# M207.net
KiCad netlist of a schematic drawn in EAGLE
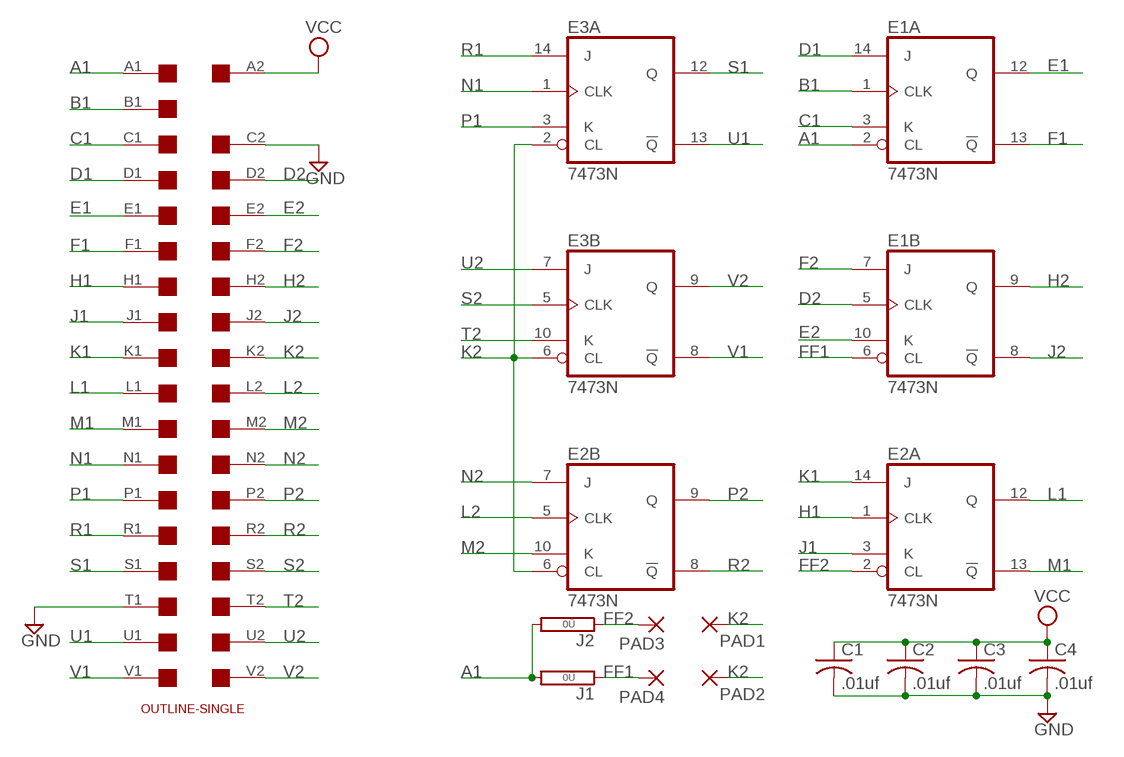
[diagram p0: schematic, sheet 1]

(export (version "E")
  (design (tool "Eeschema 10.0.6"))
  (components
    (comp (ref "C1")
      (value ".01uf")
      (footprint "eagle-import:C050-025X075")
      (libsource (lib "eagle-import") (part "C-US050-025X075"))
    )
    (comp (ref "C2")
      (value ".01uf")
      (footprint "eagle-import:C050-025X075")
      (libsource (lib "eagle-import") (part "C-US050-025X075"))
    )
    (comp (ref "C3")
      (value ".01uf")
      (footprint "eagle-import:C050-025X075")
      (libsource (lib "eagle-import") (part "C-US050-025X075"))
    )
    (comp (ref "C4")
      (value ".01uf")
      (footprint "eagle-import:C050-025X075")
      (libsource (lib "eagle-import") (part "C-US050-025X075"))
    )
    (comp (ref "E1")
      (value "7473N")
      (footprint "eagle-import:DIL14")
      (libsource (lib "eagle-import") (part "7473NLS"))
    )
    (comp (ref "E2")
      (value "7473N")
      (footprint "eagle-import:DIL14")
      (libsource (lib "eagle-import") (part "7473NLS"))
    )
    (comp (ref "E3")
      (value "7473N")
      (footprint "eagle-import:DIL14")
      (libsource (lib "eagle-import") (part "7473NLS"))
    )
    (comp (ref "J1")
      (value "0R")
      (footprint "eagle-import:0R_10")
      (libsource (lib "eagle-import") (part "0R"))
    )
    (comp (ref "J2")
      (value "0R")
      (footprint "eagle-import:0R_10")
      (libsource (lib "eagle-import") (part "0R"))
    )
    (comp (ref "PAD1")
      (value "1,6/0,8")
      (footprint "eagle-import:1,6_0,8")
      (libsource (lib "eagle-import") (part "1,6/0,8"))
    )
    (comp (ref "PAD2")
      (value "1,6/0,8")
      (footprint "eagle-import:1,6_0,8")
      (libsource (lib "eagle-import") (part "1,6/0,8"))
    )
    (comp (ref "PAD3")
      (value "1,6/0,8")
      (footprint "eagle-import:1,6_0,8")
      (libsource (lib "eagle-import") (part "1,6/0,8"))
    )
    (comp (ref "PAD4")
      (value "1,6/0,8")
      (footprint "eagle-import:1,6_0,8")
      (libsource (lib "eagle-import") (part "1,6/0,8"))
    )
    (comp (ref "U$1")
      (value "SINGLE")
      (footprint "eagle-import:EDGE-CON2")
      (libsource (lib "eagle-import") (part "SINGLE"))
    )
    (comp (ref "U$4")
      (value "OUTLINE-SINGLE")
      (footprint "eagle-import:SINGLE")
      (libsource (lib "eagle-import") (part "OUTLINE-SINGLE"))
    )
  )
  (nets
    (net (code "1") (name "/A1") (class "Default")
      (node (ref "E1") (pin "2") (pinfunction "CL_2") (pintype "input"))
      (node (ref "J1") (pin "2") (pinfunction "2_2") (pintype "passive"))
      (node (ref "J2") (pin "2") (pinfunction "2_2") (pintype "passive"))
      (node (ref "U$1") (pin "A1") (pinfunction "1_A1") (pintype "bidirectional"))
    )
    (net (code "2") (name "/B1") (class "Default")
      (node (ref "E1") (pin "1") (pinfunction "CLK_1") (pintype "input"))
      (node (ref "U$1") (pin "B1") (pinfunction "1_B1") (pintype "bidirectional"))
    )
    (net (code "3") (name "/C1") (class "Default")
      (node (ref "E1") (pin "3") (pinfunction "K_3") (pintype "input"))
      (node (ref "U$1") (pin "C1") (pinfunction "1_C1") (pintype "bidirectional"))
    )
    (net (code "4") (name "/D1") (class "Default")
      (node (ref "E1") (pin "14") (pinfunction "J_14") (pintype "input"))
      (node (ref "U$1") (pin "D1") (pinfunction "1_D1") (pintype "bidirectional"))
    )
    (net (code "5") (name "/D2") (class "Default")
      (node (ref "E1") (pin "5") (pinfunction "CLK_5") (pintype "input"))
      (node (ref "U$1") (pin "D2") (pinfunction "1_D2") (pintype "bidirectional"))
    )
    (net (code "6") (name "/E1") (class "Default")
      (node (ref "E1") (pin "12") (pinfunction "Q_12") (pintype "output"))
      (node (ref "U$1") (pin "E1") (pinfunction "1_E1") (pintype "bidirectional"))
    )
    (net (code "7") (name "/E2") (class "Default")
      (node (ref "E1") (pin "10") (pinfunction "K_10") (pintype "input"))
      (node (ref "U$1") (pin "E2") (pinfunction "1_E2") (pintype "bidirectional"))
    )
    (net (code "8") (name "/F1") (class "Default")
      (node (ref "E1") (pin "13") (pinfunction "~{Q}_13") (pintype "output"))
      (node (ref "U$1") (pin "F1") (pinfunction "1_F1") (pintype "bidirectional"))
    )
    (net (code "9") (name "/F2") (class "Default")
      (node (ref "E1") (pin "7") (pinfunction "J_7") (pintype "input"))
      (node (ref "U$1") (pin "F2") (pinfunction "1_F2") (pintype "bidirectional"))
    )
    (net (code "10") (name "/FF1") (class "Default")
      (node (ref "E1") (pin "6") (pinfunction "CL_6") (pintype "input"))
      (node (ref "J1") (pin "1") (pinfunction "1_1") (pintype "passive"))
      (node (ref "PAD4") (pin "1") (pinfunction "P_1") (pintype "passive"))
    )
    (net (code "11") (name "/FF2") (class "Default")
      (node (ref "E2") (pin "2") (pinfunction "CL_2") (pintype "input"))
      (node (ref "J2") (pin "1") (pinfunction "1_1") (pintype "passive"))
      (node (ref "PAD3") (pin "1") (pinfunction "P_1") (pintype "passive"))
    )
    (net (code "12") (name "/H1") (class "Default")
      (node (ref "E2") (pin "1") (pinfunction "CLK_1") (pintype "input"))
      (node (ref "U$1") (pin "H1") (pinfunction "1_H1") (pintype "bidirectional"))
    )
    (net (code "13") (name "/H2") (class "Default")
      (node (ref "E1") (pin "9") (pinfunction "Q_9") (pintype "output"))
      (node (ref "U$1") (pin "H2") (pinfunction "1_H2") (pintype "bidirectional"))
    )
    (net (code "14") (name "/J1") (class "Default")
      (node (ref "E2") (pin "3") (pinfunction "K_3") (pintype "input"))
      (node (ref "U$1") (pin "J1") (pinfunction "1_J1") (pintype "bidirectional"))
    )
    (net (code "15") (name "/J2") (class "Default")
      (node (ref "E1") (pin "8") (pinfunction "~{Q}_8") (pintype "output"))
      (node (ref "U$1") (pin "J2") (pinfunction "1_J2") (pintype "bidirectional"))
    )
    (net (code "16") (name "/K1") (class "Default")
      (node (ref "E2") (pin "14") (pinfunction "J_14") (pintype "input"))
      (node (ref "U$1") (pin "K1") (pinfunction "1_K1") (pintype "bidirectional"))
    )
    (net (code "17") (name "/K2") (class "Default")
      (node (ref "E2") (pin "6") (pinfunction "CL_6") (pintype "input"))
      (node (ref "E3") (pin "2") (pinfunction "CL_2") (pintype "input"))
      (node (ref "E3") (pin "6") (pinfunction "CL_6") (pintype "input"))
      (node (ref "PAD1") (pin "1") (pinfunction "P_1") (pintype "passive"))
      (node (ref "PAD2") (pin "1") (pinfunction "P_1") (pintype "passive"))
      (node (ref "U$1") (pin "K2") (pinfunction "1_K2") (pintype "bidirectional"))
    )
    (net (code "18") (name "/L1") (class "Default")
      (node (ref "E2") (pin "12") (pinfunction "Q_12") (pintype "output"))
      (node (ref "U$1") (pin "L1") (pinfunction "1_L1") (pintype "bidirectional"))
    )
    (net (code "19") (name "/L2") (class "Default")
      (node (ref "E2") (pin "5") (pinfunction "CLK_5") (pintype "input"))
      (node (ref "U$1") (pin "L2") (pinfunction "1_L2") (pintype "bidirectional"))
    )
    (net (code "20") (name "/M1") (class "Default")
      (node (ref "E2") (pin "13") (pinfunction "~{Q}_13") (pintype "output"))
      (node (ref "U$1") (pin "M1") (pinfunction "1_M1") (pintype "bidirectional"))
    )
    (net (code "21") (name "/M2") (class "Default")
      (node (ref "E2") (pin "10") (pinfunction "K_10") (pintype "input"))
      (node (ref "U$1") (pin "M2") (pinfunction "1_M2") (pintype "bidirectional"))
    )
    (net (code "22") (name "/N1") (class "Default")
      (node (ref "E3") (pin "1") (pinfunction "CLK_1") (pintype "input"))
      (node (ref "U$1") (pin "N1") (pinfunction "1_N1") (pintype "bidirectional"))
    )
    (net (code "23") (name "/N2") (class "Default")
      (node (ref "E2") (pin "7") (pinfunction "J_7") (pintype "input"))
      (node (ref "U$1") (pin "N2") (pinfunction "1_N2") (pintype "bidirectional"))
    )
    (net (code "24") (name "/P1") (class "Default")
      (node (ref "E3") (pin "3") (pinfunction "K_3") (pintype "input"))
      (node (ref "U$1") (pin "P1") (pinfunction "1_P1") (pintype "bidirectional"))
    )
    (net (code "25") (name "/P2") (class "Default")
      (node (ref "E2") (pin "9") (pinfunction "Q_9") (pintype "output"))
      (node (ref "U$1") (pin "P2") (pinfunction "1_P2") (pintype "bidirectional"))
    )
    (net (code "26") (name "/R1") (class "Default")
      (node (ref "E3") (pin "14") (pinfunction "J_14") (pintype "input"))
      (node (ref "U$1") (pin "R1") (pinfunction "1_R1") (pintype "bidirectional"))
    )
    (net (code "27") (name "/R2") (class "Default")
      (node (ref "E2") (pin "8") (pinfunction "~{Q}_8") (pintype "output"))
      (node (ref "U$1") (pin "R2") (pinfunction "1_R2") (pintype "bidirectional"))
    )
    (net (code "28") (name "/S1") (class "Default")
      (node (ref "E3") (pin "12") (pinfunction "Q_12") (pintype "output"))
      (node (ref "U$1") (pin "S1") (pinfunction "1_S1") (pintype "bidirectional"))
    )
    (net (code "29") (name "/S2") (class "Default")
      (node (ref "E3") (pin "5") (pinfunction "CLK_5") (pintype "input"))
      (node (ref "U$1") (pin "S2") (pinfunction "1_S2") (pintype "bidirectional"))
    )
    (net (code "30") (name "/T2") (class "Default")
      (node (ref "E3") (pin "10") (pinfunction "K_10") (pintype "input"))
      (node (ref "U$1") (pin "T2") (pinfunction "1_T2") (pintype "bidirectional"))
    )
    (net (code "31") (name "/U1") (class "Default")
      (node (ref "E3") (pin "13") (pinfunction "~{Q}_13") (pintype "output"))
      (node (ref "U$1") (pin "U1") (pinfunction "1_U1") (pintype "bidirectional"))
    )
    (net (code "32") (name "/U2") (class "Default")
      (node (ref "E3") (pin "7") (pinfunction "J_7") (pintype "input"))
      (node (ref "U$1") (pin "U2") (pinfunction "1_U2") (pintype "bidirectional"))
    )
    (net (code "33") (name "/V1") (class "Default")
      (node (ref "E3") (pin "8") (pinfunction "~{Q}_8") (pintype "output"))
      (node (ref "U$1") (pin "V1") (pinfunction "1_V1") (pintype "bidirectional"))
    )
    (net (code "34") (name "/V2") (class "Default")
      (node (ref "E3") (pin "9") (pinfunction "Q_9") (pintype "output"))
      (node (ref "U$1") (pin "V2") (pinfunction "1_V2") (pintype "bidirectional"))
    )
    (net (code "35") (name "GND") (class "Default")
      (node (ref "C1") (pin "2") (pinfunction "2_2") (pintype "passive"))
      (node (ref "C2") (pin "2") (pinfunction "2_2") (pintype "passive"))
      (node (ref "C3") (pin "2") (pinfunction "2_2") (pintype "passive"))
      (node (ref "C4") (pin "2") (pinfunction "2_2") (pintype "passive"))
      (node (ref "U$1") (pin "C2") (pinfunction "1_C2") (pintype "bidirectional"))
      (node (ref "U$1") (pin "T1") (pinfunction "1_T1") (pintype "bidirectional"))
    )
    (net (code "36") (name "VCC") (class "Default")
      (node (ref "C1") (pin "1") (pinfunction "1_1") (pintype "passive"))
      (node (ref "C2") (pin "1") (pinfunction "1_1") (pintype "passive"))
      (node (ref "C3") (pin "1") (pinfunction "1_1") (pintype "passive"))
      (node (ref "C4") (pin "1") (pinfunction "1_1") (pintype "passive"))
      (node (ref "U$1") (pin "A2") (pinfunction "1_A2") (pintype "bidirectional"))
    )
  )
)
